# matrix.net
KiCad netlist of a schematic drawn in EAGLE
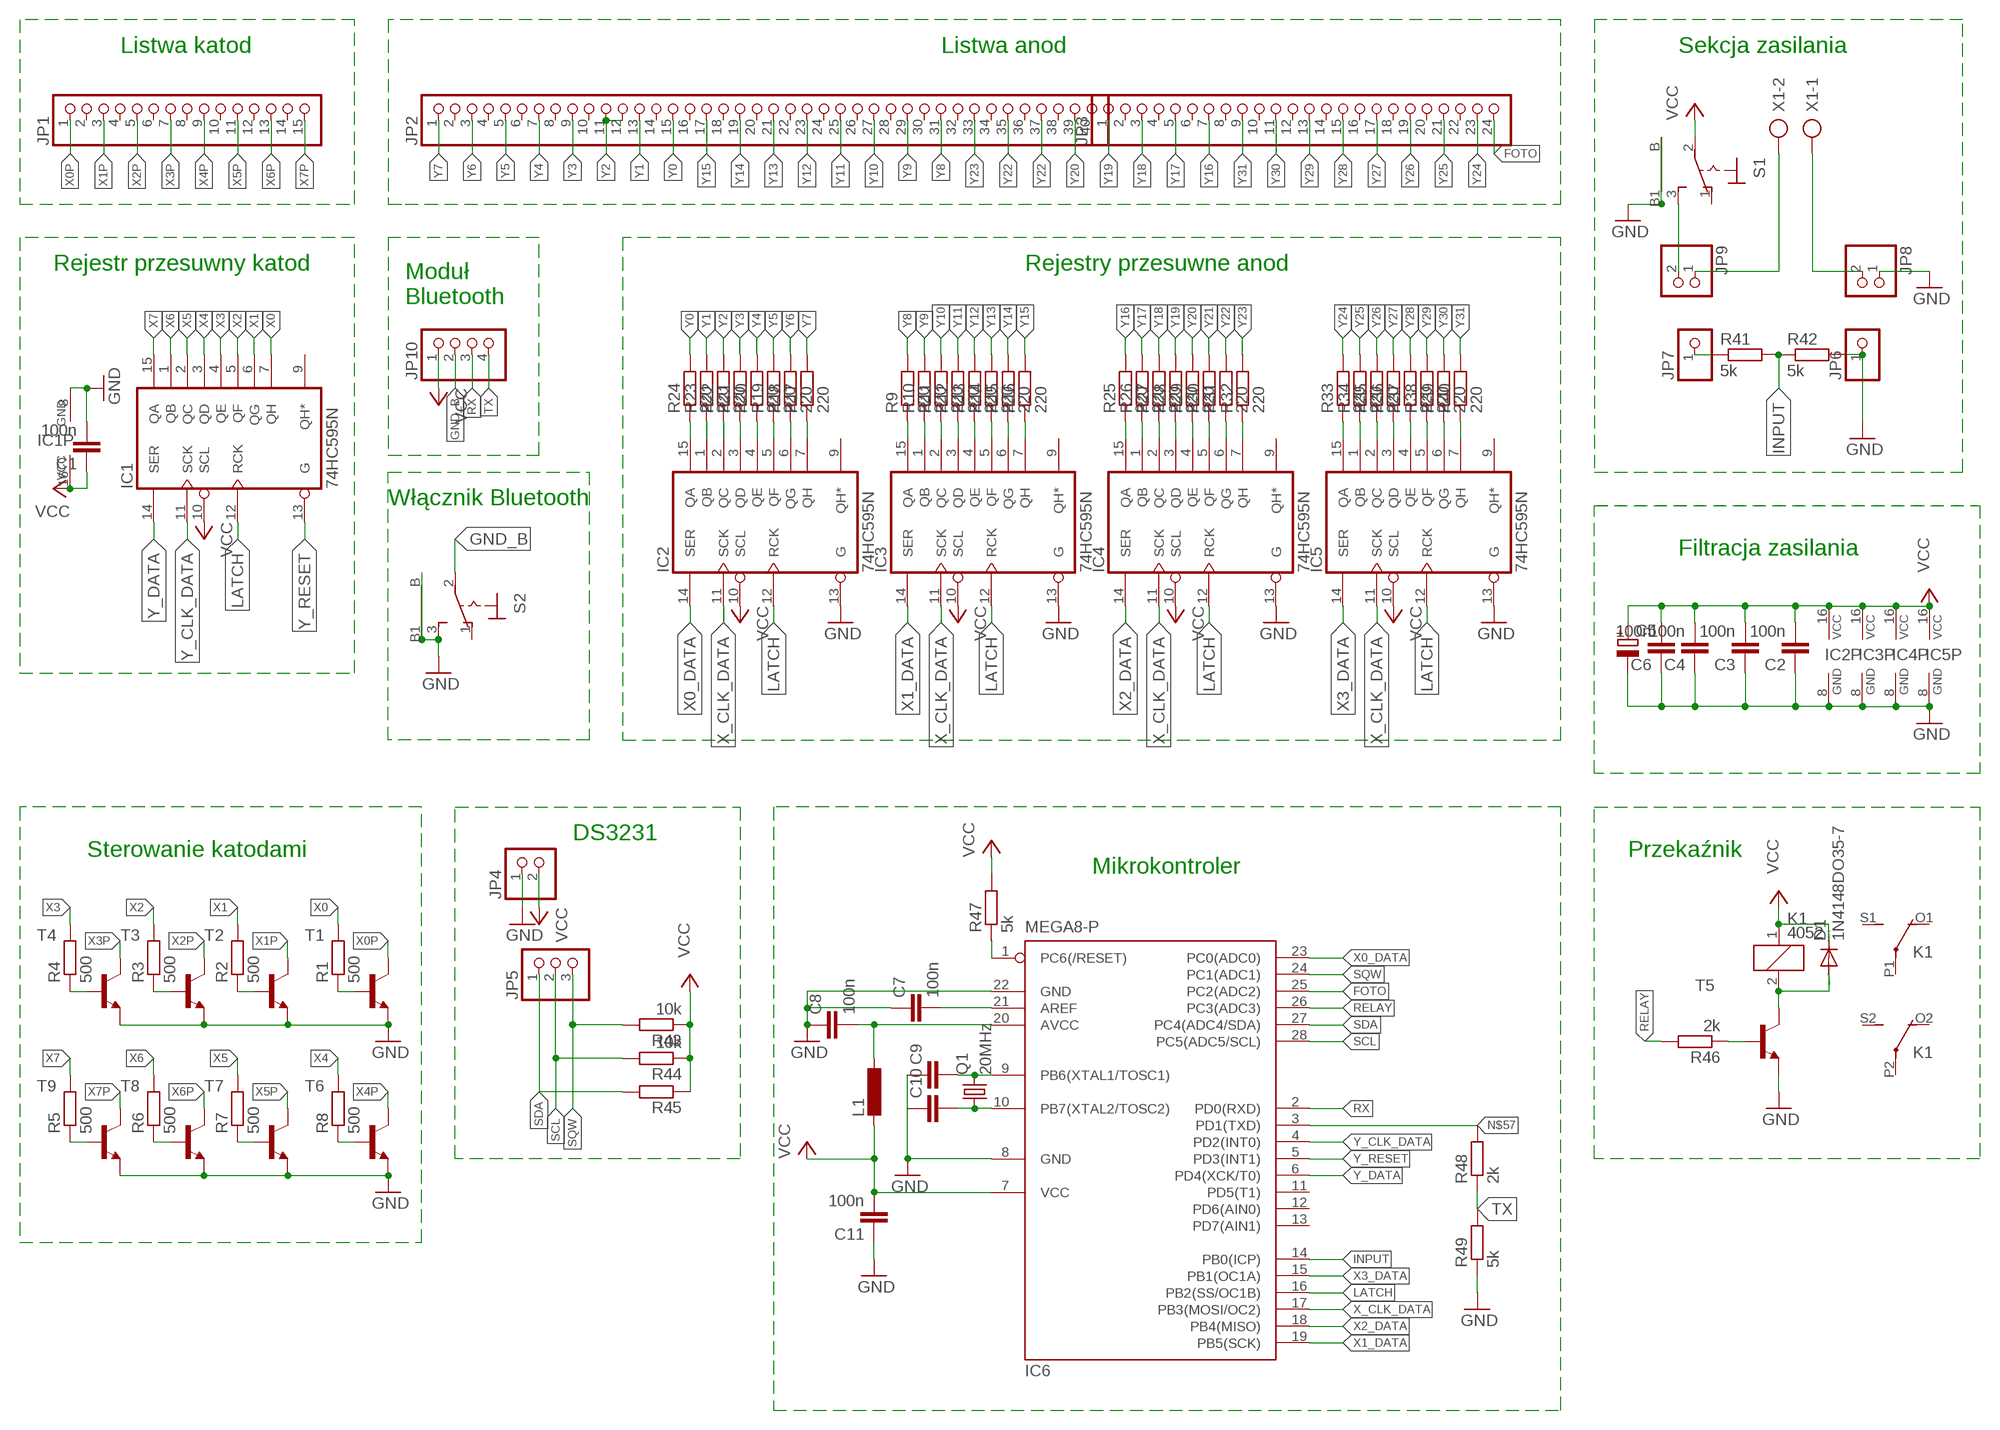
[diagram p0: schematic, sheet 1]

(export (version "E")
  (design (tool "Eeschema 10.0.6"))
  (components
    (comp (ref "C1")
      (value "100n")
      (footprint "eagle-import:C025-025X050")
      (libsource (lib "eagle-import") (part "C-EU025-025X050"))
    )
    (comp (ref "C2")
      (value "100n")
      (footprint "eagle-import:C025-025X050")
      (libsource (lib "eagle-import") (part "C-EU025-025X050"))
    )
    (comp (ref "C3")
      (value "100n")
      (footprint "eagle-import:C025-025X050")
      (libsource (lib "eagle-import") (part "C-EU025-025X050"))
    )
    (comp (ref "C4")
      (value "100n")
      (footprint "eagle-import:C025-025X050")
      (libsource (lib "eagle-import") (part "C-EU025-025X050"))
    )
    (comp (ref "C5")
      (value "CPOL-EUE2.5-7")
      (footprint "eagle-import:E2,5-7")
      (libsource (lib "eagle-import") (part "CPOL-EUE2.5-7"))
    )
    (comp (ref "C6")
      (value "100n")
      (footprint "eagle-import:C025-025X050")
      (libsource (lib "eagle-import") (part "C-EU025-025X050"))
    )
    (comp (ref "C7")
      (value "100n")
      (footprint "eagle-import:C025-025X050")
      (libsource (lib "eagle-import") (part "C-EU025-025X050"))
    )
    (comp (ref "C8")
      (value "100n")
      (footprint "eagle-import:C025-025X050")
      (libsource (lib "eagle-import") (part "C-EU025-025X050"))
    )
    (comp (ref "C9")
      (value "C-EU025-025X050")
      (footprint "eagle-import:C025-025X050")
      (libsource (lib "eagle-import") (part "C-EU025-025X050"))
    )
    (comp (ref "C10")
      (value "C-EU025-025X050")
      (footprint "eagle-import:C025-025X050")
      (libsource (lib "eagle-import") (part "C-EU025-025X050"))
    )
    (comp (ref "C11")
      (value "100n")
      (footprint "eagle-import:C025-025X050")
      (libsource (lib "eagle-import") (part "C-EU025-025X050"))
    )
    (comp (ref "D1")
      (value "1N4148DO35-7")
      (footprint "eagle-import:DO35-7")
      (libsource (lib "eagle-import") (part "1N4148DO35-7"))
    )
    (comp (ref "IC1")
      (value "74HC595N")
      (footprint "eagle-import:DIL16")
      (libsource (lib "eagle-import") (part "74595NHC"))
    )
    (comp (ref "IC2")
      (value "74HC595N")
      (footprint "eagle-import:DIL16")
      (libsource (lib "eagle-import") (part "74595NHC"))
    )
    (comp (ref "IC3")
      (value "74HC595N")
      (footprint "eagle-import:DIL16")
      (libsource (lib "eagle-import") (part "74595NHC"))
    )
    (comp (ref "IC4")
      (value "74HC595N")
      (footprint "eagle-import:DIL16")
      (libsource (lib "eagle-import") (part "74595NHC"))
    )
    (comp (ref "IC5")
      (value "74HC595N")
      (footprint "eagle-import:DIL16")
      (libsource (lib "eagle-import") (part "74595NHC"))
    )
    (comp (ref "IC6")
      (value "MEGA8-P")
      (footprint "eagle-import:DIL28-3")
      (libsource (lib "eagle-import") (part "MEGA8-P"))
    )
    (comp (ref "JP1")
      (value "PINHD-1X15")
      (footprint "eagle-import:1X15")
      (libsource (lib "eagle-import") (part "PINHD-1X15"))
    )
    (comp (ref "JP2")
      (value "PINHD-1X40")
      (footprint "eagle-import:1X40")
      (libsource (lib "eagle-import") (part "PINHD-1X40"))
    )
    (comp (ref "JP3")
      (value "PINHD-1X24")
      (footprint "eagle-import:1X24")
      (libsource (lib "eagle-import") (part "PINHD-1X24"))
    )
    (comp (ref "JP4")
      (value "PINHD-1X2")
      (footprint "eagle-import:1X02")
      (libsource (lib "eagle-import") (part "pinhead_325_PINHD-1X2"))
    )
    (comp (ref "JP5")
      (value "PINHD-1X3")
      (footprint "eagle-import:1X03")
      (libsource (lib "eagle-import") (part "PINHD-1X3"))
    )
    (comp (ref "JP6")
      (value "PINHD-1X1")
      (footprint "eagle-import:1X01")
      (libsource (lib "eagle-import") (part "PINHD-1X1"))
    )
    (comp (ref "JP7")
      (value "PINHD-1X1")
      (footprint "eagle-import:1X01")
      (libsource (lib "eagle-import") (part "PINHD-1X1"))
    )
    (comp (ref "JP8")
      (value "PINHD-1X2")
      (footprint "eagle-import:1X02")
      (libsource (lib "eagle-import") (part "PINHD-1X2"))
    )
    (comp (ref "JP9")
      (value "PINHD-1X2")
      (footprint "eagle-import:1X02")
      (libsource (lib "eagle-import") (part "PINHD-1X2"))
    )
    (comp (ref "JP10")
      (value "PINHD-1X4")
      (footprint "eagle-import:1X04")
      (libsource (lib "eagle-import") (part "PINHD-1X4"))
    )
    (comp (ref "K1")
      (value "4052")
      (footprint "eagle-import:F4052")
      (libsource (lib "eagle-import") (part "4052"))
    )
    (comp (ref "L1")
      (value "L-EU0207/10")
      (footprint "eagle-import:0207_10")
      (libsource (lib "eagle-import") (part "L-EU0207/10"))
    )
    (comp (ref "Q1")
      (value "20MHz")
      (footprint "eagle-import:HC49_S")
      (libsource (lib "eagle-import") (part "CRYSTALHC49S"))
    )
    (comp (ref "R1")
      (value "500")
      (footprint "eagle-import:0204_5")
      (libsource (lib "eagle-import") (part "R-EU_0204/5"))
    )
    (comp (ref "R2")
      (value "500")
      (footprint "eagle-import:0204_5")
      (libsource (lib "eagle-import") (part "R-EU_0204/5"))
    )
    (comp (ref "R3")
      (value "500")
      (footprint "eagle-import:0204_5")
      (libsource (lib "eagle-import") (part "R-EU_0204/5"))
    )
    (comp (ref "R4")
      (value "500")
      (footprint "eagle-import:0204_5")
      (libsource (lib "eagle-import") (part "R-EU_0204/5"))
    )
    (comp (ref "R5")
      (value "500")
      (footprint "eagle-import:0204_5")
      (libsource (lib "eagle-import") (part "R-EU_0204/5"))
    )
    (comp (ref "R6")
      (value "500")
      (footprint "eagle-import:0204_5")
      (libsource (lib "eagle-import") (part "R-EU_0204/5"))
    )
    (comp (ref "R7")
      (value "500")
      (footprint "eagle-import:0204_5")
      (libsource (lib "eagle-import") (part "R-EU_0204/5"))
    )
    (comp (ref "R8")
      (value "500")
      (footprint "eagle-import:0204_5")
      (libsource (lib "eagle-import") (part "R-EU_0204/5"))
    )
    (comp (ref "R9")
      (value "220")
      (footprint "eagle-import:0204_5")
      (libsource (lib "eagle-import") (part "R-EU_0204/5"))
    )
    (comp (ref "R10")
      (value "220")
      (footprint "eagle-import:0204_5")
      (libsource (lib "eagle-import") (part "R-EU_0204/5"))
    )
    (comp (ref "R11")
      (value "220")
      (footprint "eagle-import:0204_5")
      (libsource (lib "eagle-import") (part "R-EU_0204/5"))
    )
    (comp (ref "R12")
      (value "220")
      (footprint "eagle-import:0204_5")
      (libsource (lib "eagle-import") (part "R-EU_0204/5"))
    )
    (comp (ref "R13")
      (value "220")
      (footprint "eagle-import:0204_5")
      (libsource (lib "eagle-import") (part "R-EU_0204/5"))
    )
    (comp (ref "R14")
      (value "220")
      (footprint "eagle-import:0204_5")
      (libsource (lib "eagle-import") (part "R-EU_0204/5"))
    )
    (comp (ref "R15")
      (value "220")
      (footprint "eagle-import:0204_5")
      (libsource (lib "eagle-import") (part "R-EU_0204/5"))
    )
    (comp (ref "R16")
      (value "220")
      (footprint "eagle-import:0204_5")
      (libsource (lib "eagle-import") (part "R-EU_0204/5"))
    )
    (comp (ref "R17")
      (value "220")
      (footprint "eagle-import:0204_5")
      (libsource (lib "eagle-import") (part "R-EU_0204/5"))
    )
    (comp (ref "R18")
      (value "220")
      (footprint "eagle-import:0204V")
      (libsource (lib "eagle-import") (part "resistor_348_R-EU_0204/2V"))
    )
    (comp (ref "R19")
      (value "220")
      (footprint "eagle-import:0204V")
      (libsource (lib "eagle-import") (part "resistor_348_R-EU_0204/2V"))
    )
    (comp (ref "R20")
      (value "220")
      (footprint "eagle-import:0204_5")
      (libsource (lib "eagle-import") (part "R-EU_0204/5"))
    )
    (comp (ref "R21")
      (value "R-EU_0204/5")
      (footprint "eagle-import:0204_5")
      (libsource (lib "eagle-import") (part "R-EU_0204/5"))
    )
    (comp (ref "R22")
      (value "220")
      (footprint "eagle-import:0204_5")
      (libsource (lib "eagle-import") (part "R-EU_0204/5"))
    )
    (comp (ref "R23")
      (value "220")
      (footprint "eagle-import:0204_5")
      (libsource (lib "eagle-import") (part "R-EU_0204/5"))
    )
    (comp (ref "R24")
      (value "220")
      (footprint "eagle-import:0204_5")
      (libsource (lib "eagle-import") (part "R-EU_0204/5"))
    )
    (comp (ref "R25")
      (value "220")
      (footprint "eagle-import:0204_5")
      (libsource (lib "eagle-import") (part "R-EU_0204/5"))
    )
    (comp (ref "R26")
      (value "220")
      (footprint "eagle-import:0204_5")
      (libsource (lib "eagle-import") (part "R-EU_0204/5"))
    )
    (comp (ref "R27")
      (value "220")
      (footprint "eagle-import:0204_5")
      (libsource (lib "eagle-import") (part "R-EU_0204/5"))
    )
    (comp (ref "R28")
      (value "220")
      (footprint "eagle-import:0204_5")
      (libsource (lib "eagle-import") (part "R-EU_0204/5"))
    )
    (comp (ref "R29")
      (value "220")
      (footprint "eagle-import:0204_5")
      (libsource (lib "eagle-import") (part "R-EU_0204/5"))
    )
    (comp (ref "R30")
      (value "R-EU_0204/5")
      (footprint "eagle-import:0204_5")
      (libsource (lib "eagle-import") (part "R-EU_0204/5"))
    )
    (comp (ref "R31")
      (value "220")
      (footprint "eagle-import:0204_5")
      (libsource (lib "eagle-import") (part "resistor_348_R-EU_0204/5"))
    )
    (comp (ref "R32")
      (value "220")
      (footprint "eagle-import:0204_5")
      (libsource (lib "eagle-import") (part "R-EU_0204/5"))
    )
    (comp (ref "R33")
      (value "220")
      (footprint "eagle-import:0204_5")
      (libsource (lib "eagle-import") (part "R-EU_0204/5"))
    )
    (comp (ref "R34")
      (value "220")
      (footprint "eagle-import:0204_5")
      (libsource (lib "eagle-import") (part "R-EU_0204/5"))
    )
    (comp (ref "R35")
      (value "220")
      (footprint "eagle-import:0204_5")
      (libsource (lib "eagle-import") (part "R-EU_0204/5"))
    )
    (comp (ref "R36")
      (value "R-EU_0204/5")
      (footprint "eagle-import:0204_5")
      (libsource (lib "eagle-import") (part "R-EU_0204/5"))
    )
    (comp (ref "R37")
      (value "220")
      (footprint "eagle-import:0204_5")
      (libsource (lib "eagle-import") (part "R-EU_0204/5"))
    )
    (comp (ref "R38")
      (value "220")
      (footprint "eagle-import:0204_5")
      (libsource (lib "eagle-import") (part "R-EU_0204/5"))
    )
    (comp (ref "R39")
      (value "220")
      (footprint "eagle-import:0204_5")
      (libsource (lib "eagle-import") (part "R-EU_0204/5"))
    )
    (comp (ref "R40")
      (value "220")
      (footprint "eagle-import:0204_5")
      (libsource (lib "eagle-import") (part "R-EU_0204/5"))
    )
    (comp (ref "R41")
      (value "5k")
      (footprint "eagle-import:0204_5")
      (libsource (lib "eagle-import") (part "resistor_348_R-EU_0204/5"))
    )
    (comp (ref "R42")
      (value "5k")
      (footprint "eagle-import:0204_5")
      (libsource (lib "eagle-import") (part "resistor_348_R-EU_0204/5"))
    )
    (comp (ref "R43")
      (value "10k")
      (footprint "eagle-import:0207_7")
      (libsource (lib "eagle-import") (part "resistor_348_R-EU_0207/7"))
    )
    (comp (ref "R44")
      (value "10k")
      (footprint "eagle-import:0204_5")
      (libsource (lib "eagle-import") (part "R-EU_0204/5"))
    )
    (comp (ref "R45")
      (value "R-EU_0204/5")
      (footprint "eagle-import:0204_5")
      (libsource (lib "eagle-import") (part "R-EU_0204/5"))
    )
    (comp (ref "R46")
      (value "2k")
      (footprint "eagle-import:0207_7")
      (libsource (lib "eagle-import") (part "resistor_348_R-EU_0207/7"))
    )
    (comp (ref "R47")
      (value "5k")
      (footprint "eagle-import:0204V")
      (libsource (lib "eagle-import") (part "resistor_348_R-EU_0204/2V"))
    )
    (comp (ref "R48")
      (value "2k")
      (footprint "eagle-import:0204_5")
      (libsource (lib "eagle-import") (part "R-EU_0204/5"))
    )
    (comp (ref "R49")
      (value "5k")
      (footprint "eagle-import:0204_5")
      (libsource (lib "eagle-import") (part "R-EU_0204/5"))
    )
    (comp (ref "S1")
      (value "9070-1W")
      (footprint "eagle-import:9070-1W")
      (libsource (lib "eagle-import") (part "9070-1W"))
    )
    (comp (ref "S2")
      (value "9070-1W")
      (footprint "eagle-import:9070-1W")
      (libsource (lib "eagle-import") (part "9070-1W"))
    )
    (comp (ref "T1")
      (value "BC337-16-NPN-TO92-CBE")
      (footprint "eagle-import:TO92-CBE")
      (libsource (lib "eagle-import") (part "-NPN-TO92-CBEBC337-16"))
    )
    (comp (ref "T2")
      (value "BC337-16-NPN-TO92-CBE")
      (footprint "eagle-import:TO92-CBE")
      (libsource (lib "eagle-import") (part "-NPN-TO92-CBEBC337-16"))
    )
    (comp (ref "T3")
      (value "BC337-16-NPN-TO92-CBE")
      (footprint "eagle-import:TO92-CBE")
      (libsource (lib "eagle-import") (part "-NPN-TO92-CBEBC337-16"))
    )
    (comp (ref "T4")
      (value "BC337-16-NPN-TO92-CBE")
      (footprint "eagle-import:TO92-CBE")
      (libsource (lib "eagle-import") (part "-NPN-TO92-CBEBC337-16"))
    )
    (comp (ref "T5")
      (value "BC337-16-NPN-TO92-CBE")
      (footprint "eagle-import:TO92-CBE")
      (libsource (lib "eagle-import") (part "-NPN-TO92-CBEBC337-16"))
    )
    (comp (ref "T6")
      (value "BC337-16-NPN-TO92-CBE")
      (footprint "eagle-import:TO92-CBE")
      (libsource (lib "eagle-import") (part "-NPN-TO92-CBEBC337-16"))
    )
    (comp (ref "T7")
      (value "BC337-16-NPN-TO92-CBE")
      (footprint "eagle-import:TO92-CBE")
      (libsource (lib "eagle-import") (part "-NPN-TO92-CBEBC337-16"))
    )
    (comp (ref "T8")
      (value "BC337-16-NPN-TO92-CBE")
      (footprint "eagle-import:TO92-CBE")
      (libsource (lib "eagle-import") (part "-NPN-TO92-CBEBC337-16"))
    )
    (comp (ref "T9")
      (value "BC337-16-NPN-TO92-CBE")
      (footprint "eagle-import:TO92-CBE")
      (libsource (lib "eagle-import") (part "-NPN-TO92-CBEBC337-16"))
    )
    (comp (ref "X1")
      (value "AK300/2")
      (footprint "eagle-import:AK300_2")
      (libsource (lib "eagle-import") (part "AK300/2"))
    )
  )
  (nets
    (net (code "1") (name "FOTO") (class "Default")
      (node (ref "IC6") (pin "25") (pinfunction "PC2(ADC2)_25") (pintype "bidirectional"))
      (node (ref "JP3") (pin "24") (pinfunction "24_24") (pintype "passive"))
    )
    (net (code "2") (name "GND") (class "Default")
      (node (ref "C1") (pin "2") (pinfunction "2_2") (pintype "passive"))
      (node (ref "C10") (pin "1") (pinfunction "1_1") (pintype "passive"))
      (node (ref "C11") (pin "1") (pinfunction "1_1") (pintype "passive"))
      (node (ref "C2") (pin "1") (pinfunction "1_1") (pintype "passive"))
      (node (ref "C3") (pin "1") (pinfunction "1_1") (pintype "passive"))
      (node (ref "C4") (pin "1") (pinfunction "1_1") (pintype "passive"))
      (node (ref "C5") (pin "-") (pinfunction "-_-") (pintype "passive"))
      (node (ref "C6") (pin "1") (pinfunction "1_1") (pintype "passive"))
      (node (ref "C7") (pin "1") (pinfunction "1_1") (pintype "passive"))
      (node (ref "C8") (pin "1") (pinfunction "1_1") (pintype "passive"))
      (node (ref "C9") (pin "1") (pinfunction "1_1") (pintype "passive"))
      (node (ref "IC1") (pin "8") (pinfunction "GND_8") (pintype "power_in"))
      (node (ref "IC2") (pin "13") (pinfunction "G_13") (pintype "input"))
      (node (ref "IC2") (pin "8") (pinfunction "GND_8") (pintype "power_in"))
      (node (ref "IC3") (pin "13") (pinfunction "G_13") (pintype "input"))
      (node (ref "IC3") (pin "8") (pinfunction "GND_8") (pintype "power_in"))
      (node (ref "IC4") (pin "13") (pinfunction "G_13") (pintype "input"))
      (node (ref "IC4") (pin "8") (pinfunction "GND_8") (pintype "power_in"))
      (node (ref "IC5") (pin "13") (pinfunction "G_13") (pintype "input"))
      (node (ref "IC5") (pin "8") (pinfunction "GND_8") (pintype "power_in"))
      (node (ref "IC6") (pin "22") (pinfunction "GND_22") (pintype "power_in"))
      (node (ref "IC6") (pin "8") (pinfunction "GND_8") (pintype "power_in"))
      (node (ref "JP4") (pin "1") (pinfunction "1_1") (pintype "passive"))
      (node (ref "JP6") (pin "1") (pinfunction "1_1") (pintype "passive"))
      (node (ref "JP8") (pin "1") (pinfunction "1_1") (pintype "passive"))
      (node (ref "R42") (pin "2") (pinfunction "2_2") (pintype "passive"))
      (node (ref "R49") (pin "1") (pinfunction "1_1") (pintype "passive"))
      (node (ref "S1") (pin "B") (pinfunction "B_B") (pintype "passive"))
      (node (ref "S1") (pin "B1") (pinfunction "B1_B1") (pintype "passive"))
      (node (ref "S2") (pin "3") (pinfunction "S_3") (pintype "passive"))
      (node (ref "S2") (pin "B") (pinfunction "B_B") (pintype "passive"))
      (node (ref "S2") (pin "B1") (pinfunction "B1_B1") (pintype "passive"))
      (node (ref "T1") (pin "E") (pinfunction "E_E") (pintype "passive"))
      (node (ref "T2") (pin "E") (pinfunction "E_E") (pintype "passive"))
      (node (ref "T3") (pin "E") (pinfunction "E_E") (pintype "passive"))
      (node (ref "T4") (pin "E") (pinfunction "E_E") (pintype "passive"))
      (node (ref "T5") (pin "E") (pinfunction "E_E") (pintype "passive"))
      (node (ref "T6") (pin "E") (pinfunction "E_E") (pintype "passive"))
      (node (ref "T7") (pin "E") (pinfunction "E_E") (pintype "passive"))
      (node (ref "T8") (pin "E") (pinfunction "E_E") (pintype "passive"))
      (node (ref "T9") (pin "E") (pinfunction "E_E") (pintype "passive"))
    )
    (net (code "3") (name "GND_B") (class "Default")
      (node (ref "JP10") (pin "2") (pinfunction "2_2") (pintype "passive"))
      (node (ref "S2") (pin "2") (pinfunction "P_2") (pintype "passive"))
    )
    (net (code "4") (name "INPUT") (class "Default")
      (node (ref "IC6") (pin "14") (pinfunction "PB0(ICP)_14") (pintype "bidirectional"))
      (node (ref "R41") (pin "2") (pinfunction "2_2") (pintype "passive"))
      (node (ref "R42") (pin "1") (pinfunction "1_1") (pintype "passive"))
    )
    (net (code "5") (name "LATCH") (class "Default")
      (node (ref "IC1") (pin "12") (pinfunction "RCK_12") (pintype "input"))
      (node (ref "IC2") (pin "12") (pinfunction "RCK_12") (pintype "input"))
      (node (ref "IC3") (pin "12") (pinfunction "RCK_12") (pintype "input"))
      (node (ref "IC4") (pin "12") (pinfunction "RCK_12") (pintype "input"))
      (node (ref "IC5") (pin "12") (pinfunction "RCK_12") (pintype "input"))
      (node (ref "IC6") (pin "16") (pinfunction "PB2(SS/OC1B)_16") (pintype "bidirectional"))
    )
    (net (code "6") (name "N$57") (class "Default")
      (node (ref "IC6") (pin "3") (pinfunction "PD1(TXD)_3") (pintype "bidirectional"))
      (node (ref "R48") (pin "2") (pinfunction "2_2") (pintype "passive"))
    )
    (net (code "7") (name "Net-(D1-PadA)") (class "Default")
      (node (ref "D1") (pin "A") (pinfunction "A_A") (pintype "passive"))
      (node (ref "K1") (pin "2") (pinfunction "2_2") (pintype "passive"))
      (node (ref "T5") (pin "C") (pinfunction "C_C") (pintype "passive"))
    )
    (net (code "8") (name "Net-(IC2A-QA)") (class "Default")
      (node (ref "IC2") (pin "15") (pinfunction "QA_15") (pintype "tri_state"))
      (node (ref "R24") (pin "1") (pinfunction "1_1") (pintype "passive"))
    )
    (net (code "9") (name "Net-(IC2A-QB)") (class "Default")
      (node (ref "IC2") (pin "1") (pinfunction "QB_1") (pintype "tri_state"))
      (node (ref "R23") (pin "1") (pinfunction "1_1") (pintype "passive"))
    )
    (net (code "10") (name "Net-(IC2A-QC)") (class "Default")
      (node (ref "IC2") (pin "2") (pinfunction "QC_2") (pintype "tri_state"))
      (node (ref "R22") (pin "1") (pinfunction "1_1") (pintype "passive"))
    )
    (net (code "11") (name "Net-(IC2A-QD)") (class "Default")
      (node (ref "IC2") (pin "3") (pinfunction "QD_3") (pintype "tri_state"))
      (node (ref "R21") (pin "1") (pinfunction "1_1") (pintype "passive"))
    )
    (net (code "12") (name "Net-(IC2A-QE)") (class "Default")
      (node (ref "IC2") (pin "4") (pinfunction "QE_4") (pintype "tri_state"))
      (node (ref "R20") (pin "1") (pinfunction "1_1") (pintype "passive"))
    )
    (net (code "13") (name "Net-(IC2A-QF)") (class "Default")
      (node (ref "IC2") (pin "5") (pinfunction "QF_5") (pintype "tri_state"))
      (node (ref "R19") (pin "1") (pinfunction "1_1") (pintype "passive"))
    )
    (net (code "14") (name "Net-(IC2A-QG)") (class "Default")
      (node (ref "IC2") (pin "6") (pinfunction "QG_6") (pintype "tri_state"))
      (node (ref "R18") (pin "1") (pinfunction "1_1") (pintype "passive"))
    )
    (net (code "15") (name "Net-(IC2A-QH)") (class "Default")
      (node (ref "IC2") (pin "7") (pinfunction "QH_7") (pintype "tri_state"))
      (node (ref "R17") (pin "1") (pinfunction "1_1") (pintype "passive"))
    )
    (net (code "16") (name "Net-(IC3A-QA)") (class "Default")
      (node (ref "IC3") (pin "15") (pinfunction "QA_15") (pintype "tri_state"))
      (node (ref "R9") (pin "1") (pinfunction "1_1") (pintype "passive"))
    )
    (net (code "17") (name "Net-(IC3A-QB)") (class "Default")
      (node (ref "IC3") (pin "1") (pinfunction "QB_1") (pintype "tri_state"))
      (node (ref "R10") (pin "1") (pinfunction "1_1") (pintype "passive"))
    )
    (net (code "18") (name "Net-(IC3A-QC)") (class "Default")
      (node (ref "IC3") (pin "2") (pinfunction "QC_2") (pintype "tri_state"))
      (node (ref "R11") (pin "1") (pinfunction "1_1") (pintype "passive"))
    )
    (net (code "19") (name "Net-(IC3A-QD)") (class "Default")
      (node (ref "IC3") (pin "3") (pinfunction "QD_3") (pintype "tri_state"))
      (node (ref "R12") (pin "1") (pinfunction "1_1") (pintype "passive"))
    )
    (net (code "20") (name "Net-(IC3A-QE)") (class "Default")
      (node (ref "IC3") (pin "4") (pinfunction "QE_4") (pintype "tri_state"))
      (node (ref "R13") (pin "1") (pinfunction "1_1") (pintype "passive"))
    )
    (net (code "21") (name "Net-(IC3A-QF)") (class "Default")
      (node (ref "IC3") (pin "5") (pinfunction "QF_5") (pintype "tri_state"))
      (node (ref "R14") (pin "1") (pinfunction "1_1") (pintype "passive"))
    )
    (net (code "22") (name "Net-(IC3A-QG)") (class "Default")
      (node (ref "IC3") (pin "6") (pinfunction "QG_6") (pintype "tri_state"))
      (node (ref "R15") (pin "1") (pinfunction "1_1") (pintype "passive"))
    )
    (net (code "23") (name "Net-(IC3A-QH)") (class "Default")
      (node (ref "IC3") (pin "7") (pinfunction "QH_7") (pintype "tri_state"))
      (node (ref "R16") (pin "1") (pinfunction "1_1") (pintype "passive"))
    )
    (net (code "24") (name "Net-(IC4A-QA)") (class "Default")
      (node (ref "IC4") (pin "15") (pinfunction "QA_15") (pintype "tri_state"))
      (node (ref "R25") (pin "1") (pinfunction "1_1") (pintype "passive"))
    )
    (net (code "25") (name "Net-(IC4A-QB)") (class "Default")
      (node (ref "IC4") (pin "1") (pinfunction "QB_1") (pintype "tri_state"))
      (node (ref "R26") (pin "1") (pinfunction "1_1") (pintype "passive"))
    )
    (net (code "26") (name "Net-(IC4A-QC)") (class "Default")
      (node (ref "IC4") (pin "2") (pinfunction "QC_2") (pintype "tri_state"))
      (node (ref "R27") (pin "1") (pinfunction "1_1") (pintype "passive"))
    )
    (net (code "27") (name "Net-(IC4A-QD)") (class "Default")
      (node (ref "IC4") (pin "3") (pinfunction "QD_3") (pintype "tri_state"))
      (node (ref "R28") (pin "1") (pinfunction "1_1") (pintype "passive"))
    )
    (net (code "28") (name "Net-(IC4A-QE)") (class "Default")
      (node (ref "IC4") (pin "4") (pinfunction "QE_4") (pintype "tri_state"))
      (node (ref "R29") (pin "1") (pinfunction "1_1") (pintype "passive"))
    )
    (net (code "29") (name "Net-(IC4A-QF)") (class "Default")
      (node (ref "IC4") (pin "5") (pinfunction "QF_5") (pintype "tri_state"))
      (node (ref "R30") (pin "1") (pinfunction "1_1") (pintype "passive"))
    )
    (net (code "30") (name "Net-(IC4A-QG)") (class "Default")
      (node (ref "IC4") (pin "6") (pinfunction "QG_6") (pintype "tri_state"))
      (node (ref "R31") (pin "1") (pinfunction "1_1") (pintype "passive"))
    )
    (net (code "31") (name "Net-(IC4A-QH)") (class "Default")
      (node (ref "IC4") (pin "7") (pinfunction "QH_7") (pintype "tri_state"))
      (node (ref "R32") (pin "1") (pinfunction "1_1") (pintype "passive"))
    )
    (net (code "32") (name "Net-(IC5A-QA)") (class "Default")
      (node (ref "IC5") (pin "15") (pinfunction "QA_15") (pintype "tri_state"))
      (node (ref "R33") (pin "1") (pinfunction "1_1") (pintype "passive"))
    )
    (net (code "33") (name "Net-(IC5A-QB)") (class "Default")
      (node (ref "IC5") (pin "1") (pinfunction "QB_1") (pintype "tri_state"))
      (node (ref "R34") (pin "1") (pinfunction "1_1") (pintype "passive"))
    )
    (net (code "34") (name "Net-(IC5A-QC)") (class "Default")
      (node (ref "IC5") (pin "2") (pinfunction "QC_2") (pintype "tri_state"))
      (node (ref "R35") (pin "1") (pinfunction "1_1") (pintype "passive"))
    )
    (net (code "35") (name "Net-(IC5A-QD)") (class "Default")
      (node (ref "IC5") (pin "3") (pinfunction "QD_3") (pintype "tri_state"))
      (node (ref "R36") (pin "1") (pinfunction "1_1") (pintype "passive"))
    )
    (net (code "36") (name "Net-(IC5A-QE)") (class "Default")
      (node (ref "IC5") (pin "4") (pinfunction "QE_4") (pintype "tri_state"))
      (node (ref "R37") (pin "1") (pinfunction "1_1") (pintype "passive"))
    )
    (net (code "37") (name "Net-(IC5A-QF)") (class "Default")
      (node (ref "IC5") (pin "5") (pinfunction "QF_5") (pintype "tri_state"))
      (node (ref "R38") (pin "1") (pinfunction "1_1") (pintype "passive"))
    )
    (net (code "38") (name "Net-(IC5A-QG)") (class "Default")
      (node (ref "IC5") (pin "6") (pinfunction "QG_6") (pintype "tri_state"))
      (node (ref "R39") (pin "1") (pinfunction "1_1") (pintype "passive"))
    )
    (net (code "39") (name "Net-(IC5A-QH)") (class "Default")
      (node (ref "IC5") (pin "7") (pinfunction "QH_7") (pintype "tri_state"))
      (node (ref "R40") (pin "1") (pinfunction "1_1") (pintype "passive"))
    )
    (net (code "40") (name "Net-(IC6-AREF)") (class "Default")
      (node (ref "C7") (pin "2") (pinfunction "2_2") (pintype "passive"))
      (node (ref "IC6") (pin "21") (pinfunction "AREF_21") (pintype "passive"))
    )
    (net (code "41") (name "Net-(IC6-AVCC)") (class "Default")
      (node (ref "C8") (pin "2") (pinfunction "2_2") (pintype "passive"))
      (node (ref "IC6") (pin "20") (pinfunction "AVCC_20") (pintype "power_in"))
      (node (ref "L1") (pin "1") (pinfunction "1_1") (pintype "passive"))
    )
    (net (code "42") (name "Net-(IC6-PB6(XTAL1{slash}TOSC1))") (class "Default")
      (node (ref "C9") (pin "2") (pinfunction "2_2") (pintype "passive"))
      (node (ref "IC6") (pin "9") (pinfunction "PB6(XTAL1/TOSC1)_9") (pintype "bidirectional"))
      (node (ref "Q1") (pin "2") (pinfunction "2_2") (pintype "passive"))
    )
    (net (code "43") (name "Net-(IC6-PB7(XTAL2{slash}TOSC2))") (class "Default")
      (node (ref "C10") (pin "2") (pinfunction "2_2") (pintype "passive"))
      (node (ref "IC6") (pin "10") (pinfunction "PB7(XTAL2/TOSC2)_10") (pintype "bidirectional"))
      (node (ref "Q1") (pin "1") (pinfunction "1_1") (pintype "passive"))
    )
    (net (code "44") (name "Net-(IC6-PC6({slash}RESET))") (class "Default")
      (node (ref "IC6") (pin "1") (pinfunction "PC6(/RESET)_1") (pintype "bidirectional"))
      (node (ref "R47") (pin "1") (pinfunction "1_1") (pintype "passive"))
    )
    (net (code "45") (name "Net-(JP7-Pad1)") (class "Default")
      (node (ref "JP7") (pin "1") (pinfunction "1_1") (pintype "passive"))
      (node (ref "R41") (pin "1") (pinfunction "1_1") (pintype "passive"))
    )
    (net (code "46") (name "Net-(R1-Pad1)") (class "Default")
      (node (ref "R1") (pin "1") (pinfunction "1_1") (pintype "passive"))
      (node (ref "T1") (pin "B") (pinfunction "B_B") (pintype "passive"))
    )
    (net (code "47") (name "Net-(R2-Pad1)") (class "Default")
      (node (ref "R2") (pin "1") (pinfunction "1_1") (pintype "passive"))
      (node (ref "T2") (pin "B") (pinfunction "B_B") (pintype "passive"))
    )
    (net (code "48") (name "Net-(R3-Pad1)") (class "Default")
      (node (ref "R3") (pin "1") (pinfunction "1_1") (pintype "passive"))
      (node (ref "T3") (pin "B") (pinfunction "B_B") (pintype "passive"))
    )
    (net (code "49") (name "Net-(R4-Pad1)") (class "Default")
      (node (ref "R4") (pin "1") (pinfunction "1_1") (pintype "passive"))
      (node (ref "T4") (pin "B") (pinfunction "B_B") (pintype "passive"))
    )
    (net (code "50") (name "Net-(R5-Pad1)") (class "Default")
      (node (ref "R5") (pin "1") (pinfunction "1_1") (pintype "passive"))
      (node (ref "T9") (pin "B") (pinfunction "B_B") (pintype "passive"))
    )
    (net (code "51") (name "Net-(R6-Pad1)") (class "Default")
      (node (ref "R6") (pin "1") (pinfunction "1_1") (pintype "passive"))
      (node (ref "T8") (pin "B") (pinfunction "B_B") (pintype "passive"))
    )
    (net (code "52") (name "Net-(R7-Pad1)") (class "Default")
      (node (ref "R7") (pin "1") (pinfunction "1_1") (pintype "passive"))
      (node (ref "T7") (pin "B") (pinfunction "B_B") (pintype "passive"))
    )
    (net (code "53") (name "Net-(R8-Pad1)") (class "Default")
      (node (ref "R8") (pin "1") (pinfunction "1_1") (pintype "passive"))
      (node (ref "T6") (pin "B") (pinfunction "B_B") (pintype "passive"))
    )
    (net (code "54") (name "Net-(R46-Pad1)") (class "Default")
      (node (ref "R46") (pin "1") (pinfunction "1_1") (pintype "passive"))
      (node (ref "T5") (pin "B") (pinfunction "B_B") (pintype "passive"))
    )
    (net (code "55") (name "Net-(S1-S)") (class "Default")
      (node (ref "JP9") (pin "2") (pinfunction "2_2") (pintype "passive"))
      (node (ref "S1") (pin "3") (pinfunction "S_3") (pintype "passive"))
    )
    (net (code "56") (name "Net-(X1A-KL)") (class "Default")
      (node (ref "JP8") (pin "2") (pinfunction "2_2") (pintype "passive"))
      (node (ref "X1") (pin "1") (pinfunction "KL_1") (pintype "passive"))
    )
    (net (code "57") (name "Net-(X1B-KL)") (class "Default")
      (node (ref "JP9") (pin "1") (pinfunction "1_1") (pintype "passive"))
      (node (ref "X1") (pin "2") (pinfunction "KL_2") (pintype "passive"))
    )
    (net (code "58") (name "RELAY") (class "Default")
      (node (ref "IC6") (pin "26") (pinfunction "PC3(ADC3)_26") (pintype "bidirectional"))
      (node (ref "R46") (pin "2") (pinfunction "2_2") (pintype "passive"))
    )
    (net (code "59") (name "RX") (class "Default")
      (node (ref "IC6") (pin "2") (pinfunction "PD0(RXD)_2") (pintype "bidirectional"))
      (node (ref "JP10") (pin "3") (pinfunction "3_3") (pintype "passive"))
    )
    (net (code "60") (name "SCL") (class "Default")
      (node (ref "IC6") (pin "28") (pinfunction "PC5(ADC5/SCL)_28") (pintype "bidirectional"))
      (node (ref "JP5") (pin "2") (pinfunction "2_2") (pintype "passive"))
      (node (ref "R44") (pin "2") (pinfunction "2_2") (pintype "passive"))
    )
    (net (code "61") (name "SDA") (class "Default")
      (node (ref "IC6") (pin "27") (pinfunction "PC4(ADC4/SDA)_27") (pintype "bidirectional"))
      (node (ref "JP5") (pin "1") (pinfunction "1_1") (pintype "passive"))
      (node (ref "R45") (pin "2") (pinfunction "2_2") (pintype "passive"))
    )
    (net (code "62") (name "SQW") (class "Default")
      (node (ref "IC6") (pin "24") (pinfunction "PC1(ADC1)_24") (pintype "bidirectional"))
      (node (ref "JP5") (pin "3") (pinfunction "3_3") (pintype "passive"))
      (node (ref "R43") (pin "2") (pinfunction "2_2") (pintype "passive"))
    )
    (net (code "63") (name "TX") (class "Default")
      (node (ref "JP10") (pin "4") (pinfunction "4_4") (pintype "passive"))
      (node (ref "R48") (pin "1") (pinfunction "1_1") (pintype "passive"))
      (node (ref "R49") (pin "2") (pinfunction "2_2") (pintype "passive"))
    )
    (net (code "64") (name "VCC") (class "Default")
      (node (ref "C1") (pin "1") (pinfunction "1_1") (pintype "passive"))
      (node (ref "C11") (pin "2") (pinfunction "2_2") (pintype "passive"))
      (node (ref "C2") (pin "2") (pinfunction "2_2") (pintype "passive"))
      (node (ref "C3") (pin "2") (pinfunction "2_2") (pintype "passive"))
      (node (ref "C4") (pin "2") (pinfunction "2_2") (pintype "passive"))
      (node (ref "C5") (pin "+") (pinfunction "+_+") (pintype "passive"))
      (node (ref "C6") (pin "2") (pinfunction "2_2") (pintype "passive"))
      (node (ref "D1") (pin "C") (pinfunction "C_C") (pintype "passive"))
      (node (ref "IC1") (pin "10") (pinfunction "SCL_10") (pintype "input"))
      (node (ref "IC1") (pin "16") (pinfunction "VCC_16") (pintype "power_in"))
      (node (ref "IC2") (pin "10") (pinfunction "SCL_10") (pintype "input"))
      (node (ref "IC2") (pin "16") (pinfunction "VCC_16") (pintype "power_in"))
      (node (ref "IC3") (pin "10") (pinfunction "SCL_10") (pintype "input"))
      (node (ref "IC3") (pin "16") (pinfunction "VCC_16") (pintype "power_in"))
      (node (ref "IC4") (pin "10") (pinfunction "SCL_10") (pintype "input"))
      (node (ref "IC4") (pin "16") (pinfunction "VCC_16") (pintype "power_in"))
      (node (ref "IC5") (pin "10") (pinfunction "SCL_10") (pintype "input"))
      (node (ref "IC5") (pin "16") (pinfunction "VCC_16") (pintype "power_in"))
      (node (ref "IC6") (pin "7") (pinfunction "VCC_7") (pintype "power_in"))
      (node (ref "JP10") (pin "1") (pinfunction "1_1") (pintype "passive"))
      (node (ref "JP4") (pin "2") (pinfunction "2_2") (pintype "passive"))
      (node (ref "K1") (pin "1") (pinfunction "1_1") (pintype "passive"))
      (node (ref "L1") (pin "2") (pinfunction "2_2") (pintype "passive"))
      (node (ref "R43") (pin "1") (pinfunction "1_1") (pintype "passive"))
      (node (ref "R44") (pin "1") (pinfunction "1_1") (pintype "passive"))
      (node (ref "R45") (pin "1") (pinfunction "1_1") (pintype "passive"))
      (node (ref "R47") (pin "2") (pinfunction "2_2") (pintype "passive"))
      (node (ref "S1") (pin "2") (pinfunction "P_2") (pintype "passive"))
    )
    (net (code "65") (name "X0") (class "Default")
      (node (ref "IC1") (pin "7") (pinfunction "QH_7") (pintype "tri_state"))
      (node (ref "R1") (pin "2") (pinfunction "2_2") (pintype "passive"))
    )
    (net (code "66") (name "X0P") (class "Default")
      (node (ref "JP1") (pin "1") (pinfunction "1_1") (pintype "passive"))
      (node (ref "T1") (pin "C") (pinfunction "C_C") (pintype "passive"))
    )
    (net (code "67") (name "X0_DATA") (class "Default")
      (node (ref "IC2") (pin "14") (pinfunction "SER_14") (pintype "input"))
      (node (ref "IC6") (pin "23") (pinfunction "PC0(ADC0)_23") (pintype "bidirectional"))
    )
    (net (code "68") (name "X1") (class "Default")
      (node (ref "IC1") (pin "6") (pinfunction "QG_6") (pintype "tri_state"))
      (node (ref "R2") (pin "2") (pinfunction "2_2") (pintype "passive"))
    )
    (net (code "69") (name "X1P") (class "Default")
      (node (ref "JP1") (pin "3") (pinfunction "3_3") (pintype "passive"))
      (node (ref "T2") (pin "C") (pinfunction "C_C") (pintype "passive"))
    )
    (net (code "70") (name "X1_DATA") (class "Default")
      (node (ref "IC3") (pin "14") (pinfunction "SER_14") (pintype "input"))
      (node (ref "IC6") (pin "19") (pinfunction "PB5(SCK)_19") (pintype "bidirectional"))
    )
    (net (code "71") (name "X2") (class "Default")
      (node (ref "IC1") (pin "5") (pinfunction "QF_5") (pintype "tri_state"))
      (node (ref "R3") (pin "2") (pinfunction "2_2") (pintype "passive"))
    )
    (net (code "72") (name "X2P") (class "Default")
      (node (ref "JP1") (pin "5") (pinfunction "5_5") (pintype "passive"))
      (node (ref "T3") (pin "C") (pinfunction "C_C") (pintype "passive"))
    )
    (net (code "73") (name "X2_DATA") (class "Default")
      (node (ref "IC4") (pin "14") (pinfunction "SER_14") (pintype "input"))
      (node (ref "IC6") (pin "18") (pinfunction "PB4(MISO)_18") (pintype "bidirectional"))
    )
    (net (code "74") (name "X3") (class "Default")
      (node (ref "IC1") (pin "4") (pinfunction "QE_4") (pintype "tri_state"))
      (node (ref "R4") (pin "2") (pinfunction "2_2") (pintype "passive"))
    )
    (net (code "75") (name "X3P") (class "Default")
      (node (ref "JP1") (pin "7") (pinfunction "7_7") (pintype "passive"))
      (node (ref "T4") (pin "C") (pinfunction "C_C") (pintype "passive"))
    )
    (net (code "76") (name "X3_DATA") (class "Default")
      (node (ref "IC5") (pin "14") (pinfunction "SER_14") (pintype "input"))
      (node (ref "IC6") (pin "15") (pinfunction "PB1(OC1A)_15") (pintype "bidirectional"))
    )
    (net (code "77") (name "X4") (class "Default")
      (node (ref "IC1") (pin "3") (pinfunction "QD_3") (pintype "tri_state"))
      (node (ref "R8") (pin "2") (pinfunction "2_2") (pintype "passive"))
    )
    (net (code "78") (name "X4P") (class "Default")
      (node (ref "JP1") (pin "9") (pinfunction "9_9") (pintype "passive"))
      (node (ref "T6") (pin "C") (pinfunction "C_C") (pintype "passive"))
    )
    (net (code "79") (name "X5") (class "Default")
      (node (ref "IC1") (pin "2") (pinfunction "QC_2") (pintype "tri_state"))
      (node (ref "R7") (pin "2") (pinfunction "2_2") (pintype "passive"))
    )
    (net (code "80") (name "X5P") (class "Default")
      (node (ref "JP1") (pin "11") (pinfunction "11_11") (pintype "passive"))
      (node (ref "T7") (pin "C") (pinfunction "C_C") (pintype "passive"))
    )
    (net (code "81") (name "X6") (class "Default")
      (node (ref "IC1") (pin "1") (pinfunction "QB_1") (pintype "tri_state"))
      (node (ref "R6") (pin "2") (pinfunction "2_2") (pintype "passive"))
    )
    (net (code "82") (name "X6P") (class "Default")
      (node (ref "JP1") (pin "13") (pinfunction "13_13") (pintype "passive"))
      (node (ref "T8") (pin "C") (pinfunction "C_C") (pintype "passive"))
    )
    (net (code "83") (name "X7") (class "Default")
      (node (ref "IC1") (pin "15") (pinfunction "QA_15") (pintype "tri_state"))
      (node (ref "R5") (pin "2") (pinfunction "2_2") (pintype "passive"))
    )
    (net (code "84") (name "X7P") (class "Default")
      (node (ref "JP1") (pin "15") (pinfunction "15_15") (pintype "passive"))
      (node (ref "T9") (pin "C") (pinfunction "C_C") (pintype "passive"))
    )
    (net (code "85") (name "X_CLK_DATA") (class "Default")
      (node (ref "IC2") (pin "11") (pinfunction "SCK_11") (pintype "input"))
      (node (ref "IC3") (pin "11") (pinfunction "SCK_11") (pintype "input"))
      (node (ref "IC4") (pin "11") (pinfunction "SCK_11") (pintype "input"))
      (node (ref "IC5") (pin "11") (pinfunction "SCK_11") (pintype "input"))
      (node (ref "IC6") (pin "17") (pinfunction "PB3(MOSI/OC2)_17") (pintype "bidirectional"))
    )
    (net (code "86") (name "Y0") (class "Default")
      (node (ref "JP2") (pin "15") (pinfunction "15_15") (pintype "passive"))
      (node (ref "R24") (pin "2") (pinfunction "2_2") (pintype "passive"))
    )
    (net (code "87") (name "Y1") (class "Default")
      (node (ref "JP2") (pin "13") (pinfunction "13_13") (pintype "passive"))
      (node (ref "R23") (pin "2") (pinfunction "2_2") (pintype "passive"))
    )
    (net (code "88") (name "Y2") (class "Default")
      (node (ref "JP2") (pin "11") (pinfunction "11_11") (pintype "passive"))
      (node (ref "JP2") (pin "12") (pinfunction "12_12") (pintype "passive"))
      (node (ref "R22") (pin "2") (pinfunction "2_2") (pintype "passive"))
    )
    (net (code "89") (name "Y3") (class "Default")
      (node (ref "JP2") (pin "9") (pinfunction "9_9") (pintype "passive"))
      (node (ref "R21") (pin "2") (pinfunction "2_2") (pintype "passive"))
    )
    (net (code "90") (name "Y4") (class "Default")
      (node (ref "JP2") (pin "7") (pinfunction "7_7") (pintype "passive"))
      (node (ref "R20") (pin "2") (pinfunction "2_2") (pintype "passive"))
    )
    (net (code "91") (name "Y5") (class "Default")
      (node (ref "JP2") (pin "5") (pinfunction "5_5") (pintype "passive"))
      (node (ref "R19") (pin "2") (pinfunction "2_2") (pintype "passive"))
    )
    (net (code "92") (name "Y6") (class "Default")
      (node (ref "JP2") (pin "3") (pinfunction "3_3") (pintype "passive"))
      (node (ref "R18") (pin "2") (pinfunction "2_2") (pintype "passive"))
    )
    (net (code "93") (name "Y7") (class "Default")
      (node (ref "JP2") (pin "1") (pinfunction "1_1") (pintype "passive"))
      (node (ref "R17") (pin "2") (pinfunction "2_2") (pintype "passive"))
    )
    (net (code "94") (name "Y8") (class "Default")
      (node (ref "JP2") (pin "31") (pinfunction "31_31") (pintype "passive"))
      (node (ref "R9") (pin "2") (pinfunction "2_2") (pintype "passive"))
    )
    (net (code "95") (name "Y9") (class "Default")
      (node (ref "JP2") (pin "29") (pinfunction "29_29") (pintype "passive"))
      (node (ref "R10") (pin "2") (pinfunction "2_2") (pintype "passive"))
    )
    (net (code "96") (name "Y10") (class "Default")
      (node (ref "JP2") (pin "27") (pinfunction "27_27") (pintype "passive"))
      (node (ref "R11") (pin "2") (pinfunction "2_2") (pintype "passive"))
    )
    (net (code "97") (name "Y11") (class "Default")
      (node (ref "JP2") (pin "25") (pinfunction "25_25") (pintype "passive"))
      (node (ref "R12") (pin "2") (pinfunction "2_2") (pintype "passive"))
    )
    (net (code "98") (name "Y12") (class "Default")
      (node (ref "JP2") (pin "23") (pinfunction "23_23") (pintype "passive"))
      (node (ref "R13") (pin "2") (pinfunction "2_2") (pintype "passive"))
    )
    (net (code "99") (name "Y13") (class "Default")
      (node (ref "JP2") (pin "21") (pinfunction "21_21") (pintype "passive"))
      (node (ref "R14") (pin "2") (pinfunction "2_2") (pintype "passive"))
    )
    (net (code "100") (name "Y14") (class "Default")
      (node (ref "JP2") (pin "19") (pinfunction "19_19") (pintype "passive"))
      (node (ref "R15") (pin "2") (pinfunction "2_2") (pintype "passive"))
    )
    (net (code "101") (name "Y15") (class "Default")
      (node (ref "JP2") (pin "17") (pinfunction "17_17") (pintype "passive"))
      (node (ref "R16") (pin "2") (pinfunction "2_2") (pintype "passive"))
    )
    (net (code "102") (name "Y16") (class "Default")
      (node (ref "JP3") (pin "7") (pinfunction "7_7") (pintype "passive"))
      (node (ref "R25") (pin "2") (pinfunction "2_2") (pintype "passive"))
    )
    (net (code "103") (name "Y17") (class "Default")
      (node (ref "JP3") (pin "5") (pinfunction "5_5") (pintype "passive"))
      (node (ref "R26") (pin "2") (pinfunction "2_2") (pintype "passive"))
    )
    (net (code "104") (name "Y18") (class "Default")
      (node (ref "JP3") (pin "3") (pinfunction "3_3") (pintype "passive"))
      (node (ref "R27") (pin "2") (pinfunction "2_2") (pintype "passive"))
    )
    (net (code "105") (name "Y19") (class "Default")
      (node (ref "JP3") (pin "1") (pinfunction "1_1") (pintype "passive"))
      (node (ref "R28") (pin "2") (pinfunction "2_2") (pintype "passive"))
    )
    (net (code "106") (name "Y20") (class "Default")
      (node (ref "JP2") (pin "39") (pinfunction "39_39") (pintype "passive"))
      (node (ref "R29") (pin "2") (pinfunction "2_2") (pintype "passive"))
    )
    (net (code "107") (name "Y21") (class "Default")
      (node (ref "JP2") (pin "37") (pinfunction "37_37") (pintype "passive"))
      (node (ref "R30") (pin "2") (pinfunction "2_2") (pintype "passive"))
    )
    (net (code "108") (name "Y22") (class "Default")
      (node (ref "JP2") (pin "35") (pinfunction "35_35") (pintype "passive"))
      (node (ref "R31") (pin "2") (pinfunction "2_2") (pintype "passive"))
    )
    (net (code "109") (name "Y23") (class "Default")
      (node (ref "JP2") (pin "33") (pinfunction "33_33") (pintype "passive"))
      (node (ref "R32") (pin "2") (pinfunction "2_2") (pintype "passive"))
    )
    (net (code "110") (name "Y24") (class "Default")
      (node (ref "JP3") (pin "23") (pinfunction "23_23") (pintype "passive"))
      (node (ref "R33") (pin "2") (pinfunction "2_2") (pintype "passive"))
    )
    (net (code "111") (name "Y25") (class "Default")
      (node (ref "JP3") (pin "21") (pinfunction "21_21") (pintype "passive"))
      (node (ref "R34") (pin "2") (pinfunction "2_2") (pintype "passive"))
    )
    (net (code "112") (name "Y26") (class "Default")
      (node (ref "JP3") (pin "19") (pinfunction "19_19") (pintype "passive"))
      (node (ref "R35") (pin "2") (pinfunction "2_2") (pintype "passive"))
    )
    (net (code "113") (name "Y27") (class "Default")
      (node (ref "JP3") (pin "17") (pinfunction "17_17") (pintype "passive"))
      (node (ref "R36") (pin "2") (pinfunction "2_2") (pintype "passive"))
    )
    (net (code "114") (name "Y28") (class "Default")
      (node (ref "JP3") (pin "15") (pinfunction "15_15") (pintype "passive"))
      (node (ref "R37") (pin "2") (pinfunction "2_2") (pintype "passive"))
    )
    (net (code "115") (name "Y29") (class "Default")
      (node (ref "JP3") (pin "13") (pinfunction "13_13") (pintype "passive"))
      (node (ref "R38") (pin "2") (pinfunction "2_2") (pintype "passive"))
    )
    (net (code "116") (name "Y30") (class "Default")
      (node (ref "JP3") (pin "11") (pinfunction "11_11") (pintype "passive"))
      (node (ref "R39") (pin "2") (pinfunction "2_2") (pintype "passive"))
    )
    (net (code "117") (name "Y31") (class "Default")
      (node (ref "JP3") (pin "9") (pinfunction "9_9") (pintype "passive"))
      (node (ref "R40") (pin "2") (pinfunction "2_2") (pintype "passive"))
    )
    (net (code "118") (name "Y_CLK_DATA") (class "Default")
      (node (ref "IC1") (pin "11") (pinfunction "SCK_11") (pintype "input"))
      (node (ref "IC6") (pin "4") (pinfunction "PD2(INT0)_4") (pintype "bidirectional"))
    )
    (net (code "119") (name "Y_DATA") (class "Default")
      (node (ref "IC1") (pin "14") (pinfunction "SER_14") (pintype "input"))
      (node (ref "IC6") (pin "6") (pinfunction "PD4(XCK/T0)_6") (pintype "bidirectional"))
    )
    (net (code "120") (name "Y_RESET") (class "Default")
      (node (ref "IC1") (pin "13") (pinfunction "G_13") (pintype "input"))
      (node (ref "IC6") (pin "5") (pinfunction "PD3(INT1)_5") (pintype "bidirectional"))
    )
    (net (code "121") (name "unconnected-(IC1A-QH*-Pad9)") (class "Default")
      (node (ref "IC1") (pin "9") (pinfunction "QH*_9") (pintype "tri_state"))
    )
    (net (code "122") (name "unconnected-(IC2A-QH*-Pad9)") (class "Default")
      (node (ref "IC2") (pin "9") (pinfunction "QH*_9") (pintype "tri_state"))
    )
    (net (code "123") (name "unconnected-(IC3A-QH*-Pad9)") (class "Default")
      (node (ref "IC3") (pin "9") (pinfunction "QH*_9") (pintype "tri_state"))
    )
    (net (code "124") (name "unconnected-(IC4A-QH*-Pad9)") (class "Default")
      (node (ref "IC4") (pin "9") (pinfunction "QH*_9") (pintype "tri_state"))
    )
    (net (code "125") (name "unconnected-(IC5A-QH*-Pad9)") (class "Default")
      (node (ref "IC5") (pin "9") (pinfunction "QH*_9") (pintype "tri_state"))
    )
    (net (code "126") (name "unconnected-(IC6-PD5(T1)-Pad11)") (class "Default")
      (node (ref "IC6") (pin "11") (pinfunction "PD5(T1)_11") (pintype "bidirectional"))
    )
    (net (code "127") (name "unconnected-(IC6-PD6(AIN0)-Pad12)") (class "Default")
      (node (ref "IC6") (pin "12") (pinfunction "PD6(AIN0)_12") (pintype "bidirectional"))
    )
    (net (code "128") (name "unconnected-(IC6-PD7(AIN1)-Pad13)") (class "Default")
      (node (ref "IC6") (pin "13") (pinfunction "PD7(AIN1)_13") (pintype "bidirectional"))
    )
    (net (code "129") (name "unconnected-(JP1-Pad2)") (class "Default")
      (node (ref "JP1") (pin "2") (pinfunction "2_2") (pintype "passive"))
    )
    (net (code "130") (name "unconnected-(JP1-Pad4)") (class "Default")
      (node (ref "JP1") (pin "4") (pinfunction "4_4") (pintype "passive"))
    )
    (net (code "131") (name "unconnected-(JP1-Pad6)") (class "Default")
      (node (ref "JP1") (pin "6") (pinfunction "6_6") (pintype "passive"))
    )
    (net (code "132") (name "unconnected-(JP1-Pad8)") (class "Default")
      (node (ref "JP1") (pin "8") (pinfunction "8_8") (pintype "passive"))
    )
    (net (code "133") (name "unconnected-(JP1-Pad10)") (class "Default")
      (node (ref "JP1") (pin "10") (pinfunction "10_10") (pintype "passive"))
    )
    (net (code "134") (name "unconnected-(JP1-Pad12)") (class "Default")
      (node (ref "JP1") (pin "12") (pinfunction "12_12") (pintype "passive"))
    )
    (net (code "135") (name "unconnected-(JP1-Pad14)") (class "Default")
      (node (ref "JP1") (pin "14") (pinfunction "14_14") (pintype "passive"))
    )
    (net (code "136") (name "unconnected-(JP2-Pad2)") (class "Default")
      (node (ref "JP2") (pin "2") (pinfunction "2_2") (pintype "passive"))
    )
    (net (code "137") (name "unconnected-(JP2-Pad4)") (class "Default")
      (node (ref "JP2") (pin "4") (pinfunction "4_4") (pintype "passive"))
    )
    (net (code "138") (name "unconnected-(JP2-Pad6)") (class "Default")
      (node (ref "JP2") (pin "6") (pinfunction "6_6") (pintype "passive"))
    )
    (net (code "139") (name "unconnected-(JP2-Pad8)") (class "Default")
      (node (ref "JP2") (pin "8") (pinfunction "8_8") (pintype "passive"))
    )
    (net (code "140") (name "unconnected-(JP2-Pad10)") (class "Default")
      (node (ref "JP2") (pin "10") (pinfunction "10_10") (pintype "passive"))
    )
    (net (code "141") (name "unconnected-(JP2-Pad14)") (class "Default")
      (node (ref "JP2") (pin "14") (pinfunction "14_14") (pintype "passive"))
    )
    (net (code "142") (name "unconnected-(JP2-Pad16)") (class "Default")
      (node (ref "JP2") (pin "16") (pinfunction "16_16") (pintype "passive"))
    )
    (net (code "143") (name "unconnected-(JP2-Pad18)") (class "Default")
      (node (ref "JP2") (pin "18") (pinfunction "18_18") (pintype "passive"))
    )
    (net (code "144") (name "unconnected-(JP2-Pad20)") (class "Default")
      (node (ref "JP2") (pin "20") (pinfunction "20_20") (pintype "passive"))
    )
    (net (code "145") (name "unconnected-(JP2-Pad22)") (class "Default")
      (node (ref "JP2") (pin "22") (pinfunction "22_22") (pintype "passive"))
    )
    (net (code "146") (name "unconnected-(JP2-Pad24)") (class "Default")
      (node (ref "JP2") (pin "24") (pinfunction "24_24") (pintype "passive"))
    )
    (net (code "147") (name "unconnected-(JP2-Pad26)") (class "Default")
      (node (ref "JP2") (pin "26") (pinfunction "26_26") (pintype "passive"))
    )
    (net (code "148") (name "unconnected-(JP2-Pad28)") (class "Default")
      (node (ref "JP2") (pin "28") (pinfunction "28_28") (pintype "passive"))
    )
    (net (code "149") (name "unconnected-(JP2-Pad30)") (class "Default")
      (node (ref "JP2") (pin "30") (pinfunction "30_30") (pintype "passive"))
    )
    (net (code "150") (name "unconnected-(JP2-Pad32)") (class "Default")
      (node (ref "JP2") (pin "32") (pinfunction "32_32") (pintype "passive"))
    )
    (net (code "151") (name "unconnected-(JP2-Pad34)") (class "Default")
      (node (ref "JP2") (pin "34") (pinfunction "34_34") (pintype "passive"))
    )
    (net (code "152") (name "unconnected-(JP2-Pad36)") (class "Default")
      (node (ref "JP2") (pin "36") (pinfunction "36_36") (pintype "passive"))
    )
    (net (code "153") (name "unconnected-(JP2-Pad38)") (class "Default")
      (node (ref "JP2") (pin "38") (pinfunction "38_38") (pintype "passive"))
    )
    (net (code "154") (name "unconnected-(JP2-Pad40)") (class "Default")
      (node (ref "JP2") (pin "40") (pinfunction "40_40") (pintype "passive"))
    )
    (net (code "155") (name "unconnected-(JP3-Pad2)") (class "Default")
      (node (ref "JP3") (pin "2") (pinfunction "2_2") (pintype "passive"))
    )
    (net (code "156") (name "unconnected-(JP3-Pad4)") (class "Default")
      (node (ref "JP3") (pin "4") (pinfunction "4_4") (pintype "passive"))
    )
    (net (code "157") (name "unconnected-(JP3-Pad6)") (class "Default")
      (node (ref "JP3") (pin "6") (pinfunction "6_6") (pintype "passive"))
    )
    (net (code "158") (name "unconnected-(JP3-Pad8)") (class "Default")
      (node (ref "JP3") (pin "8") (pinfunction "8_8") (pintype "passive"))
    )
    (net (code "159") (name "unconnected-(JP3-Pad10)") (class "Default")
      (node (ref "JP3") (pin "10") (pinfunction "10_10") (pintype "passive"))
    )
    (net (code "160") (name "unconnected-(JP3-Pad12)") (class "Default")
      (node (ref "JP3") (pin "12") (pinfunction "12_12") (pintype "passive"))
    )
    (net (code "161") (name "unconnected-(JP3-Pad14)") (class "Default")
      (node (ref "JP3") (pin "14") (pinfunction "14_14") (pintype "passive"))
    )
    (net (code "162") (name "unconnected-(JP3-Pad16)") (class "Default")
      (node (ref "JP3") (pin "16") (pinfunction "16_16") (pintype "passive"))
    )
    (net (code "163") (name "unconnected-(JP3-Pad18)") (class "Default")
      (node (ref "JP3") (pin "18") (pinfunction "18_18") (pintype "passive"))
    )
    (net (code "164") (name "unconnected-(JP3-Pad20)") (class "Default")
      (node (ref "JP3") (pin "20") (pinfunction "20_20") (pintype "passive"))
    )
    (net (code "165") (name "unconnected-(JP3-Pad22)") (class "Default")
      (node (ref "JP3") (pin "22") (pinfunction "22_22") (pintype "passive"))
    )
    (net (code "166") (name "unconnected-(K1B-O-PadO1)") (class "Default")
      (node (ref "K1") (pin "O1") (pinfunction "O_O1") (pintype "passive"))
    )
    (net (code "167") (name "unconnected-(K1B-P-PadP1)") (class "Default")
      (node (ref "K1") (pin "P1") (pinfunction "P_P1") (pintype "passive"))
    )
    (net (code "168") (name "unconnected-(K1B-S-PadS1)") (class "Default")
      (node (ref "K1") (pin "S1") (pinfunction "S_S1") (pintype "passive"))
    )
    (net (code "169") (name "unconnected-(K1C-O-PadO2)") (class "Default")
      (node (ref "K1") (pin "O2") (pinfunction "O_O2") (pintype "passive"))
    )
    (net (code "170") (name "unconnected-(K1C-P-PadP2)") (class "Default")
      (node (ref "K1") (pin "P2") (pinfunction "P_P2") (pintype "passive"))
    )
    (net (code "171") (name "unconnected-(K1C-S-PadS2)") (class "Default")
      (node (ref "K1") (pin "S2") (pinfunction "S_S2") (pintype "passive"))
    )
    (net (code "172") (name "unconnected-(S1-O-Pad1)") (class "Default")
      (node (ref "S1") (pin "1") (pinfunction "O_1") (pintype "passive"))
    )
    (net (code "173") (name "unconnected-(S2-O-Pad1)") (class "Default")
      (node (ref "S2") (pin "1") (pinfunction "O_1") (pintype "passive"))
    )
  )
)
